# Codec.net
KiCad netlist of a schematic drawn in Altium Designer
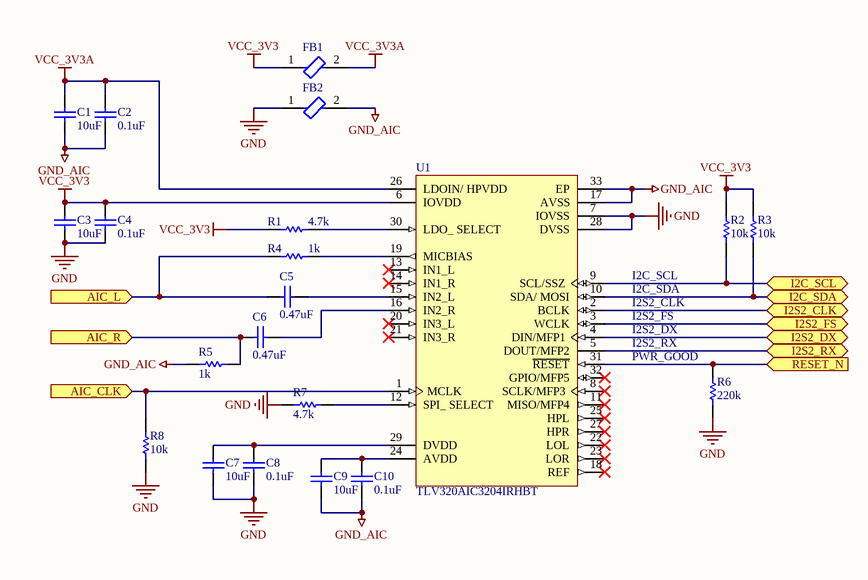
[diagram p0: Codec.SchDoc]

(export (version "E")
  (design (tool "Eeschema 10.0.6"))
  (components
    (comp (ref "C1")
      (value "10uF")
      (footprint "0805_C_S")
      (description "Capacitor")
      (fields (field (name "PUBLISHER") "Altium Limited"))
      (libsource (lib "Miscellaneous Devices") (part "Cap"))
    )
    (comp (ref "C2")
      (value "0.1uF")
      (footprint "0805_C_S")
      (description "Capacitor")
      (fields (field (name "PUBLISHER") "Altium Limited"))
      (libsource (lib "Miscellaneous Devices") (part "Cap"))
    )
    (comp (ref "C3")
      (value "10uF")
      (footprint "0805_C_S")
      (description "Capacitor")
      (fields (field (name "PUBLISHER") "Altium Limited"))
      (libsource (lib "Miscellaneous Devices") (part "Cap"))
    )
    (comp (ref "C4")
      (value "0.1uF")
      (footprint "0805_C_S")
      (description "Capacitor")
      (fields (field (name "PUBLISHER") "Altium Limited"))
      (libsource (lib "Miscellaneous Devices") (part "Cap"))
    )
    (comp (ref "C5")
      (value "0.47uF")
      (footprint "0805_C_S")
      (description "Capacitor")
      (fields (field (name "PUBLISHER") "Altium Limited"))
      (libsource (lib "Miscellaneous Devices") (part "Cap"))
    )
    (comp (ref "C6")
      (value "0.47uF")
      (footprint "0805_C_S")
      (description "Capacitor")
      (fields (field (name "PUBLISHER") "Altium Limited"))
      (libsource (lib "Miscellaneous Devices") (part "Cap"))
    )
    (comp (ref "C7")
      (value "10uF")
      (footprint "0805_C_S")
      (description "Capacitor")
      (fields (field (name "PUBLISHER") "Altium Limited"))
      (libsource (lib "Miscellaneous Devices") (part "Cap"))
    )
    (comp (ref "C8")
      (value "0.1uF")
      (footprint "0805_C_S")
      (description "Capacitor")
      (fields (field (name "PUBLISHER") "Altium Limited"))
      (libsource (lib "Miscellaneous Devices") (part "Cap"))
    )
    (comp (ref "C9")
      (value "10uF")
      (footprint "0805_C_S")
      (description "Capacitor")
      (fields (field (name "PUBLISHER") "Altium Limited"))
      (libsource (lib "Miscellaneous Devices") (part "Cap"))
    )
    (comp (ref "C10")
      (value "0.1uF")
      (footprint "0805_C_S")
      (description "Capacitor")
      (fields (field (name "PUBLISHER") "Altium Limited"))
      (libsource (lib "Miscellaneous Devices") (part "Cap"))
    )
    (comp (ref "FB1")
      (value "BLM21AG151SN1D")
      (footprint "FP-BLM21-0_2-t0_85-e0_5-MFG")
      (description "Chip Ferrite Bead, 0805, 150Ω @ 100MHz, 0.09Ω, 25%, 1A")
      (fields (field (name "TOLERANCE") "25%"))
      (libsource (lib "Altium Content Vault") (part "5f30dd21d616792df468990f7003faa"))
    )
    (comp (ref "FB2")
      (value "BLM21AG151SN1D")
      (footprint "FP-BLM21-0_2-t0_85-e0_5-MFG")
      (description "Chip Ferrite Bead, 0805, 150Ω @ 100MHz, 0.09Ω, 25%, 1A")
      (fields (field (name "TOLERANCE") "25%"))
      (libsource (lib "Altium Content Vault") (part "5f30dd21d616792df468990f7003faa"))
    )
    (comp (ref "R1")
      (value "4.7k")
      (footprint "0805_R_S")
      (description "Resistor")
      (fields (field (name "PUBLISHER") "Altium Limited"))
      (libsource (lib "Miscellaneous Devices") (part "Res1"))
    )
    (comp (ref "R2")
      (value "10k")
      (footprint "0805_R_S")
      (description "Resistor")
      (fields (field (name "PUBLISHER") "Altium Limited"))
      (libsource (lib "Miscellaneous Devices") (part "Res1"))
    )
    (comp (ref "R3")
      (value "10k")
      (footprint "0805_R_S")
      (description "Resistor")
      (fields (field (name "PUBLISHER") "Altium Limited"))
      (libsource (lib "Miscellaneous Devices") (part "Res1"))
    )
    (comp (ref "R4")
      (value "1k")
      (footprint "0805_R_S")
      (description "Resistor")
      (fields (field (name "PUBLISHER") "Altium Limited"))
      (libsource (lib "Miscellaneous Devices") (part "Res1"))
    )
    (comp (ref "R5")
      (value "1k")
      (footprint "0805_R_S")
      (description "Resistor")
      (fields (field (name "PUBLISHER") "Altium Limited"))
      (libsource (lib "Miscellaneous Devices") (part "Res1"))
    )
    (comp (ref "R6")
      (value "220k")
      (footprint "0805_R_S")
      (description "Resistor")
      (fields (field (name "PUBLISHER") "Altium Limited"))
      (libsource (lib "Miscellaneous Devices") (part "Res1"))
    )
    (comp (ref "R7")
      (value "4.7k")
      (footprint "0805_R_S")
      (description "Resistor")
      (fields (field (name "PUBLISHER") "Altium Limited"))
      (libsource (lib "Miscellaneous Devices") (part "Res1"))
    )
    (comp (ref "R8")
      (value "10k")
      (footprint "0805_R_S")
      (description "Resistor")
      (fields (field (name "PUBLISHER") "Altium Limited"))
      (libsource (lib "Miscellaneous Devices") (part "Res1"))
    )
    (comp (ref "U1")
      (value "TLV320AIC3204IRHBT")
      (footprint "RHB0032E_V")
      (fields (field (name "MANUFACTURER") "Texas Instruments"))
      (libsource (lib "Altium Content Vault") (part "TI-TLV320AIC3204RHB32-3450X3450TP"))
    )
  )
  (nets
    (net (code "1") (name "/AIC_CLK") (class "Default")
      (node (ref "R8") (pin "2") (pinfunction "2_2") (pintype "passive"))
      (node (ref "U1") (pin "1") (pinfunction "MCLK_1") (pintype "input"))
    )
    (net (code "2") (name "/AIC_L") (class "Default")
      (node (ref "C5") (pin "2") (pinfunction "2_2") (pintype "passive"))
      (node (ref "R4") (pin "2") (pinfunction "2_2") (pintype "passive"))
    )
    (net (code "3") (name "/AIC_R") (class "Default")
      (node (ref "C6") (pin "2") (pinfunction "2_2") (pintype "passive"))
      (node (ref "R5") (pin "1") (pinfunction "1_1") (pintype "passive"))
    )
    (net (code "4") (name "/I2C_SCL") (class "Default")
      (node (ref "R2") (pin "1") (pinfunction "1_1") (pintype "passive"))
      (node (ref "U1") (pin "9") (pinfunction "SCL/SSZ_9") (pintype "bidirectional"))
    )
    (net (code "5") (name "/I2C_SDA") (class "Default")
      (node (ref "R3") (pin "1") (pinfunction "1_1") (pintype "passive"))
      (node (ref "U1") (pin "10") (pinfunction "SDA/_MOSI_10") (pintype "bidirectional"))
    )
    (net (code "6") (name "/I2S2_CLK") (class "Default")
      (node (ref "U1") (pin "2") (pinfunction "BCLK_2") (pintype "bidirectional"))
    )
    (net (code "7") (name "/I2S2_DX") (class "Default")
      (node (ref "U1") (pin "4") (pinfunction "DIN/MFP1_4") (pintype "input"))
    )
    (net (code "8") (name "/I2S2_FS") (class "Default")
      (node (ref "U1") (pin "3") (pinfunction "WCLK_3") (pintype "bidirectional"))
    )
    (net (code "9") (name "/I2S2_RX") (class "Default")
      (node (ref "U1") (pin "5") (pinfunction "DOUT/MFP2_5") (pintype "tri_state"))
    )
    (net (code "10") (name "/RESET_N") (class "Default")
      (node (ref "R6") (pin "2") (pinfunction "2_2") (pintype "passive"))
      (node (ref "U1") (pin "31") (pinfunction "~{RESET}_31") (pintype "input"))
    )
    (net (code "11") (name "GND") (class "Default")
      (node (ref "C3") (pin "1") (pinfunction "1_1") (pintype "passive"))
      (node (ref "C4") (pin "1") (pinfunction "1_1") (pintype "passive"))
      (node (ref "C7") (pin "1") (pinfunction "1_1") (pintype "passive"))
      (node (ref "C8") (pin "1") (pinfunction "1_1") (pintype "passive"))
      (node (ref "FB2") (pin "1") (pinfunction "1_1") (pintype "passive"))
      (node (ref "R6") (pin "1") (pinfunction "1_1") (pintype "passive"))
      (node (ref "R7") (pin "1") (pinfunction "1_1") (pintype "passive"))
      (node (ref "R8") (pin "1") (pinfunction "1_1") (pintype "passive"))
      (node (ref "U1") (pin "28") (pinfunction "DVSS_28") (pintype "power_in"))
      (node (ref "U1") (pin "7") (pinfunction "IOVSS_7") (pintype "power_in"))
    )
    (net (code "12") (name "GND_AIC") (class "Default")
      (node (ref "C1") (pin "1") (pinfunction "1_1") (pintype "passive"))
      (node (ref "C10") (pin "1") (pinfunction "1_1") (pintype "passive"))
      (node (ref "C2") (pin "1") (pinfunction "1_1") (pintype "passive"))
      (node (ref "C9") (pin "1") (pinfunction "1_1") (pintype "passive"))
      (node (ref "FB2") (pin "2") (pinfunction "2_2") (pintype "passive"))
      (node (ref "R5") (pin "2") (pinfunction "2_2") (pintype "passive"))
      (node (ref "U1") (pin "17") (pinfunction "AVSS_17") (pintype "power_in"))
      (node (ref "U1") (pin "33") (pinfunction "EP_33") (pintype "passive"))
    )
    (net (code "13") (name "Net-(U1-AVDD)") (class "Default")
      (node (ref "C10") (pin "2") (pinfunction "2_2") (pintype "passive"))
      (node (ref "C9") (pin "2") (pinfunction "2_2") (pintype "passive"))
      (node (ref "U1") (pin "24") (pinfunction "AVDD_24") (pintype "power_in"))
    )
    (net (code "14") (name "Net-(U1-DVDD)") (class "Default")
      (node (ref "C7") (pin "2") (pinfunction "2_2") (pintype "passive"))
      (node (ref "C8") (pin "2") (pinfunction "2_2") (pintype "passive"))
      (node (ref "U1") (pin "29") (pinfunction "DVDD_29") (pintype "power_in"))
    )
    (net (code "15") (name "Net-(U1-IN2_L)") (class "Default")
      (node (ref "C5") (pin "1") (pinfunction "1_1") (pintype "passive"))
      (node (ref "U1") (pin "15") (pinfunction "IN2_L_15") (pintype "input"))
    )
    (net (code "16") (name "Net-(U1-IN2_R)") (class "Default")
      (node (ref "C6") (pin "1") (pinfunction "1_1") (pintype "passive"))
      (node (ref "U1") (pin "16") (pinfunction "IN2_R_16") (pintype "input"))
    )
    (net (code "17") (name "Net-(U1-LDO__SELECT)") (class "Default")
      (node (ref "R1") (pin "1") (pinfunction "1_1") (pintype "passive"))
      (node (ref "U1") (pin "30") (pinfunction "LDO__SELECT_30") (pintype "input"))
    )
    (net (code "18") (name "Net-(U1-MICBIAS)") (class "Default")
      (node (ref "R4") (pin "1") (pinfunction "1_1") (pintype "passive"))
      (node (ref "U1") (pin "19") (pinfunction "MICBIAS_19") (pintype "output"))
    )
    (net (code "19") (name "Net-(U1-SPI__SELECT)") (class "Default")
      (node (ref "R7") (pin "2") (pinfunction "2_2") (pintype "passive"))
      (node (ref "U1") (pin "12") (pinfunction "SPI__SELECT_12") (pintype "input"))
    )
    (net (code "20") (name "VCC_3V3") (class "Default")
      (node (ref "C3") (pin "2") (pinfunction "2_2") (pintype "passive"))
      (node (ref "C4") (pin "2") (pinfunction "2_2") (pintype "passive"))
      (node (ref "FB1") (pin "1") (pinfunction "1_1") (pintype "passive"))
      (node (ref "R1") (pin "2") (pinfunction "2_2") (pintype "passive"))
      (node (ref "R2") (pin "2") (pinfunction "2_2") (pintype "passive"))
      (node (ref "R3") (pin "2") (pinfunction "2_2") (pintype "passive"))
      (node (ref "U1") (pin "6") (pinfunction "IOVDD_6") (pintype "power_in"))
    )
    (net (code "21") (name "VCC_3V3A") (class "Default")
      (node (ref "C1") (pin "2") (pinfunction "2_2") (pintype "passive"))
      (node (ref "C2") (pin "2") (pinfunction "2_2") (pintype "passive"))
      (node (ref "FB1") (pin "2") (pinfunction "2_2") (pintype "passive"))
      (node (ref "U1") (pin "26") (pinfunction "LDOIN/_HPVDD_26") (pintype "power_in"))
    )
    (net (code "22") (name "unconnected-(U1-GPIO{slash}MFP5-Pad32)") (class "Default")
      (node (ref "U1") (pin "32") (pinfunction "GPIO/MFP5_32") (pintype "bidirectional+no_connect"))
    )
    (net (code "23") (name "unconnected-(U1-HPL-Pad25)") (class "Default")
      (node (ref "U1") (pin "25") (pinfunction "HPL_25") (pintype "output+no_connect"))
    )
    (net (code "24") (name "unconnected-(U1-HPR-Pad27)") (class "Default")
      (node (ref "U1") (pin "27") (pinfunction "HPR_27") (pintype "output+no_connect"))
    )
    (net (code "25") (name "unconnected-(U1-IN1_L-Pad13)") (class "Default")
      (node (ref "U1") (pin "13") (pinfunction "IN1_L_13") (pintype "input+no_connect"))
    )
    (net (code "26") (name "unconnected-(U1-IN1_R-Pad14)") (class "Default")
      (node (ref "U1") (pin "14") (pinfunction "IN1_R_14") (pintype "input+no_connect"))
    )
    (net (code "27") (name "unconnected-(U1-IN3_L-Pad20)") (class "Default")
      (node (ref "U1") (pin "20") (pinfunction "IN3_L_20") (pintype "input+no_connect"))
    )
    (net (code "28") (name "unconnected-(U1-IN3_R-Pad21)") (class "Default")
      (node (ref "U1") (pin "21") (pinfunction "IN3_R_21") (pintype "input+no_connect"))
    )
    (net (code "29") (name "unconnected-(U1-LOL-Pad22)") (class "Default")
      (node (ref "U1") (pin "22") (pinfunction "LOL_22") (pintype "output+no_connect"))
    )
    (net (code "30") (name "unconnected-(U1-LOR-Pad23)") (class "Default")
      (node (ref "U1") (pin "23") (pinfunction "LOR_23") (pintype "output+no_connect"))
    )
    (net (code "31") (name "unconnected-(U1-MISO{slash}MFP4-Pad11)") (class "Default")
      (node (ref "U1") (pin "11") (pinfunction "MISO/MFP4_11") (pintype "output+no_connect"))
    )
    (net (code "32") (name "unconnected-(U1-REF-Pad18)") (class "Default")
      (node (ref "U1") (pin "18") (pinfunction "REF_18") (pintype "output+no_connect"))
    )
    (net (code "33") (name "unconnected-(U1-SCLK{slash}MFP3-Pad8)") (class "Default")
      (node (ref "U1") (pin "8") (pinfunction "SCLK/MFP3_8") (pintype "input+no_connect"))
    )
  )
)
